# sw63_mk3.net
KiCad netlist of a schematic drawn in EAGLE
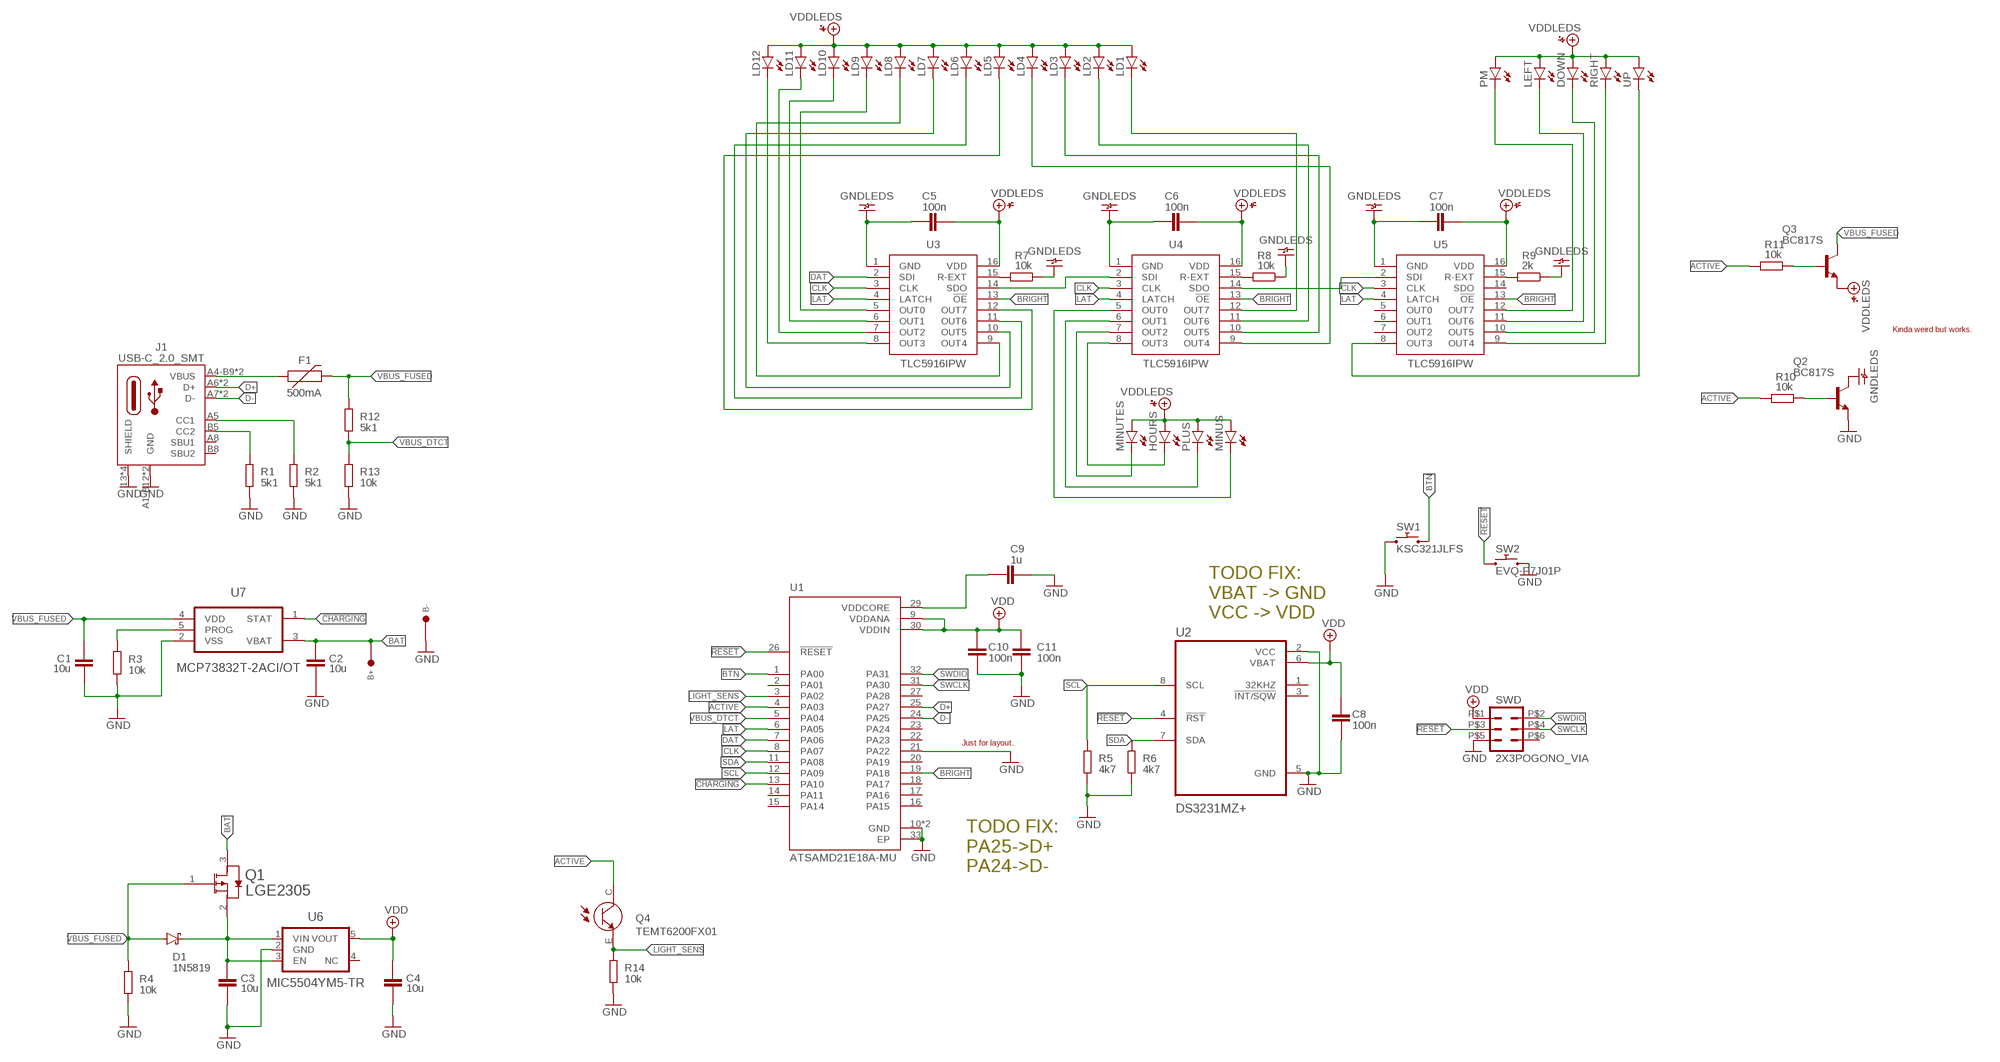
[diagram p0: schematic, sheet 1]

(export (version "E")
  (design (tool "Eeschema 10.0.6"))
  (components
    (comp (ref "B+")
      (value "TEST_PIN_LARGE")
      (footprint "eagle-import:TEST_PIN_2.0")
      (libsource (lib "eagle-import") (part "TEST_PIN_LARGE"))
    )
    (comp (ref "B-")
      (value "TEST_PIN_LARGE")
      (footprint "eagle-import:TEST_PIN_2.0")
      (libsource (lib "eagle-import") (part "TEST_PIN_LARGE"))
    )
    (comp (ref "C1")
      (value "10u")
      (footprint "eagle-import:CAPACITOR0805")
      (libsource (lib "eagle-import") (part "CAPACITOR0805"))
    )
    (comp (ref "C2")
      (value "10u")
      (footprint "eagle-import:CAPACITOR0805")
      (libsource (lib "eagle-import") (part "CAPACITOR0805"))
    )
    (comp (ref "C3")
      (value "10u")
      (footprint "eagle-import:CAPACITOR0805")
      (libsource (lib "eagle-import") (part "CAPACITOR0805"))
    )
    (comp (ref "C4")
      (value "10u")
      (footprint "eagle-import:CAPACITOR0805")
      (libsource (lib "eagle-import") (part "CAPACITOR0805"))
    )
    (comp (ref "C5")
      (value "100n")
      (footprint "eagle-import:CAPACITOR0603")
      (libsource (lib "eagle-import") (part "CAPACITOR0603"))
    )
    (comp (ref "C6")
      (value "100n")
      (footprint "eagle-import:CAPACITOR0603")
      (libsource (lib "eagle-import") (part "CAPACITOR0603"))
    )
    (comp (ref "C7")
      (value "100n")
      (footprint "eagle-import:CAPACITOR0603")
      (libsource (lib "eagle-import") (part "CAPACITOR0603"))
    )
    (comp (ref "C8")
      (value "100n")
      (footprint "eagle-import:CAPACITOR0603")
      (libsource (lib "eagle-import") (part "CAPACITOR0603"))
    )
    (comp (ref "C9")
      (value "1u")
      (footprint "eagle-import:CAPACITOR0603")
      (libsource (lib "eagle-import") (part "CAPACITOR0603"))
    )
    (comp (ref "C10")
      (value "100n")
      (footprint "eagle-import:CAPACITOR0603")
      (libsource (lib "eagle-import") (part "CAPACITOR0603"))
    )
    (comp (ref "C11")
      (value "100n")
      (footprint "eagle-import:CAPACITOR0603")
      (libsource (lib "eagle-import") (part "CAPACITOR0603"))
    )
    (comp (ref "D1")
      (value "1N5819")
      (footprint "eagle-import:SOD123")
      (libsource (lib "eagle-import") (part "SCHOTTKY_DIODE"))
    )
    (comp (ref "DOWN")
      (value "LED_RECT-3.2X2")
      (footprint "eagle-import:LED_RECT_3.2X2")
      (libsource (lib "eagle-import") (part "LED_RECT-3.2X2"))
    )
    (comp (ref "F1")
      (value "500mA")
      (footprint "eagle-import:PTC0805")
      (libsource (lib "eagle-import") (part "PTC"))
    )
    (comp (ref "HOURS")
      (value "LED_THT-5MM_B")
      (footprint "eagle-import:LED_5MM_BLUE")
      (libsource (lib "eagle-import") (part "LED_THT-5MM_B"))
    )
    (comp (ref "J1")
      (value "USB-C_2.0_SMT")
      (footprint "eagle-import:USB-C_FULL_SMT")
      (libsource (lib "eagle-import") (part "USB-C_2.0_SMT"))
    )
    (comp (ref "LD1")
      (value "LED_SMT_1206")
      (footprint "eagle-import:LED_1206")
      (libsource (lib "eagle-import") (part "LED_SMT_1206"))
    )
    (comp (ref "LD2")
      (value "LED_SMT_1206")
      (footprint "eagle-import:LED_1206")
      (libsource (lib "eagle-import") (part "LED_SMT_1206"))
    )
    (comp (ref "LD3")
      (value "LED_SMT_1206")
      (footprint "eagle-import:LED_1206")
      (libsource (lib "eagle-import") (part "LED_SMT_1206"))
    )
    (comp (ref "LD4")
      (value "LED_SMT_1206")
      (footprint "eagle-import:LED_1206")
      (libsource (lib "eagle-import") (part "LED_SMT_1206"))
    )
    (comp (ref "LD5")
      (value "LED_SMT_1206")
      (footprint "eagle-import:LED_1206")
      (libsource (lib "eagle-import") (part "LED_SMT_1206"))
    )
    (comp (ref "LD6")
      (value "LED_SMT_1206")
      (footprint "eagle-import:LED_1206")
      (libsource (lib "eagle-import") (part "LED_SMT_1206"))
    )
    (comp (ref "LD7")
      (value "LED_SMT_1206")
      (footprint "eagle-import:LED_1206")
      (libsource (lib "eagle-import") (part "LED_SMT_1206"))
    )
    (comp (ref "LD8")
      (value "LED_SMT_1206")
      (footprint "eagle-import:LED_1206")
      (libsource (lib "eagle-import") (part "LED_SMT_1206"))
    )
    (comp (ref "LD9")
      (value "LED_SMT_1206")
      (footprint "eagle-import:LED_1206")
      (libsource (lib "eagle-import") (part "LED_SMT_1206"))
    )
    (comp (ref "LD10")
      (value "LED_SMT_1206")
      (footprint "eagle-import:LED_1206")
      (libsource (lib "eagle-import") (part "LED_SMT_1206"))
    )
    (comp (ref "LD11")
      (value "LED_SMT_1206")
      (footprint "eagle-import:LED_1206")
      (libsource (lib "eagle-import") (part "LED_SMT_1206"))
    )
    (comp (ref "LD12")
      (value "LED_SMT_1206")
      (footprint "eagle-import:LED_1206")
      (libsource (lib "eagle-import") (part "LED_SMT_1206"))
    )
    (comp (ref "LEFT")
      (value "LED_RECT-3.2X2")
      (footprint "eagle-import:LED_RECT_3.2X2")
      (libsource (lib "eagle-import") (part "LED_RECT-3.2X2"))
    )
    (comp (ref "MINUS")
      (value "LED_THT-5MM_R")
      (footprint "eagle-import:LED_5MM_RED")
      (libsource (lib "eagle-import") (part "LED_THT-5MM_R"))
    )
    (comp (ref "MINUTES")
      (value "LED_THT-5MM_Y")
      (footprint "eagle-import:LED_5MM_YELLOW")
      (libsource (lib "eagle-import") (part "LED_THT-5MM_Y"))
    )
    (comp (ref "PLUS")
      (value "LED_THT-5MM_G")
      (footprint "eagle-import:LED_5MM_GREEN")
      (libsource (lib "eagle-import") (part "LED_THT-5MM_G"))
    )
    (comp (ref "PM")
      (value "LED_THT-3MM_ALT")
      (footprint "eagle-import:LED_3MM_ALT")
      (libsource (lib "eagle-import") (part "LED_THT-3MM_ALT"))
    )
    (comp (ref "Q1")
      (value "LGE2305")
      (footprint "eagle-import:SOT23")
      (libsource (lib "eagle-import") (part "LGE2305"))
    )
    (comp (ref "Q2")
      (value "BC817S")
      (footprint "eagle-import:SOT23")
      (libsource (lib "eagle-import") (part "BC817S"))
    )
    (comp (ref "Q3")
      (value "BC817S")
      (footprint "eagle-import:SOT23")
      (libsource (lib "eagle-import") (part "BC817S"))
    )
    (comp (ref "Q4")
      (value "TEMT6200FX01")
      (footprint "eagle-import:TEMT6200FX01")
      (fields (field (name "MF") "Vishay Semiconductor"))
      (libsource (lib "eagle-import") (part "TEMT6200FX01"))
    )
    (comp (ref "R1")
      (value "5k1")
      (footprint "eagle-import:RESISTOR0603")
      (libsource (lib "eagle-import") (part "RESISTOR0603"))
    )
    (comp (ref "R2")
      (value "5k1")
      (footprint "eagle-import:RESISTOR0603")
      (libsource (lib "eagle-import") (part "RESISTOR0603"))
    )
    (comp (ref "R3")
      (value "10k")
      (footprint "eagle-import:RESISTOR0603")
      (libsource (lib "eagle-import") (part "RESISTOR0603"))
    )
    (comp (ref "R4")
      (value "10k")
      (footprint "eagle-import:RESISTOR0603")
      (libsource (lib "eagle-import") (part "RESISTOR0603"))
    )
    (comp (ref "R5")
      (value "4k7")
      (footprint "eagle-import:RESISTOR0603")
      (libsource (lib "eagle-import") (part "RESISTOR0603"))
    )
    (comp (ref "R6")
      (value "4k7")
      (footprint "eagle-import:RESISTOR0603")
      (libsource (lib "eagle-import") (part "RESISTOR0603"))
    )
    (comp (ref "R7")
      (value "10k")
      (footprint "eagle-import:RESISTOR0603")
      (libsource (lib "eagle-import") (part "RESISTOR0603"))
    )
    (comp (ref "R8")
      (value "10k")
      (footprint "eagle-import:RESISTOR0603")
      (libsource (lib "eagle-import") (part "RESISTOR0603"))
    )
    (comp (ref "R9")
      (value "2k")
      (footprint "eagle-import:RESISTOR0603")
      (libsource (lib "eagle-import") (part "RESISTOR0603"))
    )
    (comp (ref "R10")
      (value "10k")
      (footprint "eagle-import:RESISTOR0603")
      (libsource (lib "eagle-import") (part "RESISTOR0603"))
    )
    (comp (ref "R11")
      (value "10k")
      (footprint "eagle-import:RESISTOR0603")
      (libsource (lib "eagle-import") (part "RESISTOR0603"))
    )
    (comp (ref "R12")
      (value "5k1")
      (footprint "eagle-import:RESISTOR0603")
      (libsource (lib "eagle-import") (part "RESISTOR0603"))
    )
    (comp (ref "R13")
      (value "10k")
      (footprint "eagle-import:RESISTOR0603")
      (libsource (lib "eagle-import") (part "RESISTOR0603"))
    )
    (comp (ref "R14")
      (value "10k")
      (footprint "eagle-import:RESISTOR0603")
      (libsource (lib "eagle-import") (part "RESISTOR0603"))
    )
    (comp (ref "RIGHT")
      (value "LED_RECT-3.2X2")
      (footprint "eagle-import:LED_RECT_3.2X2")
      (libsource (lib "eagle-import") (part "LED_RECT-3.2X2"))
    )
    (comp (ref "SW1")
      (value "KSC321JLFS")
      (footprint "eagle-import:KSC3XXJ")
      (libsource (lib "eagle-import") (part "KSC3XXJ"))
    )
    (comp (ref "SW2")
      (value "EVQ-P7J01P")
      (footprint "eagle-import:EVQ-P7J01P")
      (libsource (lib "eagle-import") (part "EVQ-P7J01P"))
    )
    (comp (ref "SWD")
      (value "2X3POGONO_VIA")
      (footprint "eagle-import:2X3_POGO_NO_VIA")
      (libsource (lib "eagle-import") (part "2X3POGONO_VIA"))
    )
    (comp (ref "U1")
      (value "ATSAMD21E18A-MU")
      (footprint "eagle-import:QFN50P500X500X100-33N")
      (fields (field (name "DIGIKEY_PART_NUMBER") "ATSAMD21E18A-MU-ND") (field (name "MF") "Microchip"))
      (libsource (lib "eagle-import") (part "ATSAMD21E18A-MU"))
    )
    (comp (ref "U2")
      (value "DS3231MZ+")
      (footprint "eagle-import:SO8")
      (fields
        (field (name "DIGI-KEY_PART_NUMBER") "DS3231MZ+-ND")
        (field (name "MF") "Maxim Integrated Products")
      )
      (libsource (lib "eagle-import") (part "DS3231MZ+"))
    )
    (comp (ref "U3")
      (value "TLC5916IPW")
      (footprint "eagle-import:TSSOP16")
      (libsource (lib "eagle-import") (part "TLC5916IPW"))
    )
    (comp (ref "U4")
      (value "TLC5916IPW")
      (footprint "eagle-import:TSSOP16")
      (libsource (lib "eagle-import") (part "TLC5916IPW"))
    )
    (comp (ref "U5")
      (value "TLC5916IPW")
      (footprint "eagle-import:TSSOP16")
      (libsource (lib "eagle-import") (part "TLC5916IPW"))
    )
    (comp (ref "U6")
      (value "MIC5504YM5-TR")
      (footprint "eagle-import:SOT23-5")
      (libsource (lib "eagle-import") (part "MIC5504YM5-TR"))
    )
    (comp (ref "U7")
      (value "MCP73832T-2ACI/OT")
      (footprint "eagle-import:SOT23-5")
      (fields (field (name "MPN") "MCP73831T-2ACI/OT"))
      (libsource (lib "eagle-import") (part "MCP73831T-2ACI"))
    )
    (comp (ref "UP")
      (value "LED_RECT-3.2X2")
      (footprint "eagle-import:LED_RECT_3.2X2")
      (libsource (lib "eagle-import") (part "LED_RECT-3.2X2"))
    )
  )
  (nets
    (net (code "1") (name "/~{CHARGING}") (class "Default")
      (node (ref "U1") (pin "13") (pinfunction "PA10_13") (pintype "bidirectional"))
      (node (ref "U7") (pin "1") (pinfunction "STAT_1") (pintype "output"))
    )
    (net (code "2") (name "/~{RESET}") (class "Default")
      (node (ref "SW2") (pin "1_1") (pinfunction "1_1_1") (pintype "passive"))
      (node (ref "SW2") (pin "1_2") (pinfunction "1_1_2") (pintype "passive"))
      (node (ref "SWD") (pin "P$3") (pinfunction "3_P$3") (pintype "passive"))
      (node (ref "U1") (pin "26") (pinfunction "~{RESET}_26") (pintype "input"))
      (node (ref "U2") (pin "4") (pinfunction "~{RST}_4") (pintype "bidirectional"))
    )
    (net (code "3") (name "ACTIVE") (class "Default")
      (node (ref "Q4") (pin "C") (pinfunction "C_C") (pintype "passive"))
      (node (ref "R10") (pin "2") (pinfunction "2_2") (pintype "passive"))
      (node (ref "R11") (pin "2") (pinfunction "2_2") (pintype "passive"))
      (node (ref "U1") (pin "4") (pinfunction "PA03_4") (pintype "bidirectional"))
    )
    (net (code "4") (name "BAT") (class "Default")
      (node (ref "B+") (pin "P$1") (pinfunction "P$1_P$1") (pintype "bidirectional"))
      (node (ref "C2") (pin "1") (pinfunction "1_1") (pintype "passive"))
      (node (ref "Q1") (pin "3") (pinfunction "DRAIN_3") (pintype "passive"))
      (node (ref "U7") (pin "3") (pinfunction "VBAT_3") (pintype "output"))
    )
    (net (code "5") (name "BRIGHT") (class "Default")
      (node (ref "U1") (pin "19") (pinfunction "PA18_19") (pintype "bidirectional"))
      (node (ref "U3") (pin "13") (pinfunction "~{OE}_13") (pintype "input"))
      (node (ref "U4") (pin "13") (pinfunction "~{OE}_13") (pintype "input"))
      (node (ref "U5") (pin "13") (pinfunction "~{OE}_13") (pintype "input"))
    )
    (net (code "6") (name "BTN") (class "Default")
      (node (ref "SW1") (pin "2") (pinfunction "2_2") (pintype "passive"))
      (node (ref "SW1") (pin "4") (pinfunction "2_4") (pintype "passive"))
      (node (ref "U1") (pin "1") (pinfunction "PA00_1") (pintype "bidirectional"))
    )
    (net (code "7") (name "CLK") (class "Default")
      (node (ref "U1") (pin "8") (pinfunction "PA07_8") (pintype "bidirectional"))
      (node (ref "U3") (pin "3") (pinfunction "CLK_3") (pintype "input"))
      (node (ref "U4") (pin "3") (pinfunction "CLK_3") (pintype "input"))
      (node (ref "U5") (pin "3") (pinfunction "CLK_3") (pintype "input"))
    )
    (net (code "8") (name "D+") (class "Default")
      (node (ref "J1") (pin "A6") (pinfunction "D+_A6") (pintype "bidirectional"))
      (node (ref "J1") (pin "B6") (pinfunction "D+_B6") (pintype "bidirectional"))
      (node (ref "U1") (pin "25") (pinfunction "PA27_25") (pintype "bidirectional"))
    )
    (net (code "9") (name "D-") (class "Default")
      (node (ref "J1") (pin "A7") (pinfunction "D-_A7") (pintype "bidirectional"))
      (node (ref "J1") (pin "B7") (pinfunction "D-_B7") (pintype "bidirectional"))
      (node (ref "U1") (pin "24") (pinfunction "PA25_24") (pintype "bidirectional"))
    )
    (net (code "10") (name "DAT") (class "Default")
      (node (ref "U1") (pin "7") (pinfunction "PA06_7") (pintype "bidirectional"))
      (node (ref "U3") (pin "2") (pinfunction "SDI_2") (pintype "input"))
    )
    (net (code "11") (name "GND") (class "Default")
      (node (ref "B-") (pin "P$1") (pinfunction "P$1_P$1") (pintype "bidirectional"))
      (node (ref "C1") (pin "2") (pinfunction "2_2") (pintype "passive"))
      (node (ref "C10") (pin "1") (pinfunction "1_1") (pintype "passive"))
      (node (ref "C11") (pin "1") (pinfunction "1_1") (pintype "passive"))
      (node (ref "C2") (pin "2") (pinfunction "2_2") (pintype "passive"))
      (node (ref "C3") (pin "2") (pinfunction "2_2") (pintype "passive"))
      (node (ref "C4") (pin "2") (pinfunction "2_2") (pintype "passive"))
      (node (ref "C8") (pin "2") (pinfunction "2_2") (pintype "passive"))
      (node (ref "C9") (pin "1") (pinfunction "1_1") (pintype "passive"))
      (node (ref "J1") (pin "13") (pinfunction "SHIELD_13") (pintype "bidirectional"))
      (node (ref "J1") (pin "14") (pinfunction "SHIELD_14") (pintype "bidirectional"))
      (node (ref "J1") (pin "15") (pinfunction "SHIELD_15") (pintype "bidirectional"))
      (node (ref "J1") (pin "16") (pinfunction "SHIELD_16") (pintype "bidirectional"))
      (node (ref "J1") (pin "A1-B12") (pinfunction "GND_A1-B12") (pintype "passive"))
      (node (ref "J1") (pin "B1-A12") (pinfunction "GND_B1-A12") (pintype "passive"))
      (node (ref "Q2") (pin "2") (pinfunction "E_2") (pintype "passive"))
      (node (ref "R1") (pin "1") (pinfunction "1_1") (pintype "passive"))
      (node (ref "R13") (pin "1") (pinfunction "1_1") (pintype "passive"))
      (node (ref "R14") (pin "1") (pinfunction "1_1") (pintype "passive"))
      (node (ref "R2") (pin "1") (pinfunction "1_1") (pintype "passive"))
      (node (ref "R3") (pin "1") (pinfunction "1_1") (pintype "passive"))
      (node (ref "R4") (pin "1") (pinfunction "1_1") (pintype "passive"))
      (node (ref "R5") (pin "1") (pinfunction "1_1") (pintype "passive"))
      (node (ref "R6") (pin "1") (pinfunction "1_1") (pintype "passive"))
      (node (ref "SW1") (pin "1") (pinfunction "1_1") (pintype "passive"))
      (node (ref "SW1") (pin "3") (pinfunction "1_3") (pintype "passive"))
      (node (ref "SW2") (pin "2_1") (pinfunction "2_2_1") (pintype "passive"))
      (node (ref "SW2") (pin "2_2") (pinfunction "2_2_2") (pintype "passive"))
      (node (ref "SWD") (pin "P$5") (pinfunction "5_P$5") (pintype "passive"))
      (node (ref "U1") (pin "10") (pinfunction "GND_10") (pintype "power_in"))
      (node (ref "U1") (pin "21") (pinfunction "PA22_21") (pintype "bidirectional"))
      (node (ref "U1") (pin "28") (pinfunction "GND_28") (pintype "power_in"))
      (node (ref "U1") (pin "33") (pinfunction "EP_33") (pintype "power_in"))
      (node (ref "U2") (pin "2") (pinfunction "VCC_2") (pintype "power_in"))
      (node (ref "U2") (pin "5") (pinfunction "GND_5") (pintype "power_in"))
      (node (ref "U6") (pin "2") (pinfunction "GND_2") (pintype "power_in"))
      (node (ref "U7") (pin "2") (pinfunction "VSS_2") (pintype "power_in"))
    )
    (net (code "12") (name "GNDLEDS") (class "Default")
      (node (ref "C5") (pin "1") (pinfunction "1_1") (pintype "passive"))
      (node (ref "C6") (pin "1") (pinfunction "1_1") (pintype "passive"))
      (node (ref "C7") (pin "1") (pinfunction "1_1") (pintype "passive"))
      (node (ref "Q2") (pin "3") (pinfunction "C_3") (pintype "passive"))
      (node (ref "R7") (pin "1") (pinfunction "1_1") (pintype "passive"))
      (node (ref "R8") (pin "1") (pinfunction "1_1") (pintype "passive"))
      (node (ref "R9") (pin "1") (pinfunction "1_1") (pintype "passive"))
      (node (ref "U3") (pin "1") (pinfunction "GND_1") (pintype "power_in"))
      (node (ref "U4") (pin "1") (pinfunction "GND_1") (pintype "power_in"))
      (node (ref "U5") (pin "1") (pinfunction "GND_1") (pintype "power_in"))
    )
    (net (code "13") (name "LAT") (class "Default")
      (node (ref "U1") (pin "6") (pinfunction "PA05_6") (pintype "bidirectional"))
      (node (ref "U3") (pin "4") (pinfunction "LATCH_4") (pintype "input"))
      (node (ref "U4") (pin "4") (pinfunction "LATCH_4") (pintype "input"))
      (node (ref "U5") (pin "4") (pinfunction "LATCH_4") (pintype "input"))
    )
    (net (code "14") (name "LIGHT_SENS") (class "Default")
      (node (ref "Q4") (pin "E") (pinfunction "E_E") (pintype "passive"))
      (node (ref "R14") (pin "2") (pinfunction "2_2") (pintype "passive"))
      (node (ref "U1") (pin "3") (pinfunction "PA02_3") (pintype "bidirectional"))
    )
    (net (code "15") (name "Net-(DOWN-C)") (class "Default")
      (node (ref "DOWN") (pin "K") (pinfunction "C_K") (pintype "passive"))
      (node (ref "U5") (pin "10") (pinfunction "OUT5_10") (pintype "output"))
    )
    (net (code "16") (name "Net-(F1-1)") (class "Default")
      (node (ref "F1") (pin "2") (pinfunction "1_2") (pintype "bidirectional"))
      (node (ref "J1") (pin "A4-B9") (pinfunction "VBUS_A4-B9") (pintype "power_in"))
      (node (ref "J1") (pin "B4-A9") (pinfunction "VBUS_B4-A9") (pintype "power_in"))
    )
    (net (code "17") (name "Net-(HOURS-C)") (class "Default")
      (node (ref "HOURS") (pin "K") (pinfunction "C_K") (pintype "passive"))
      (node (ref "U4") (pin "8") (pinfunction "OUT3_8") (pintype "output"))
    )
    (net (code "18") (name "Net-(J1-CC1)") (class "Default")
      (node (ref "J1") (pin "A5") (pinfunction "CC1_A5") (pintype "bidirectional"))
      (node (ref "R2") (pin "2") (pinfunction "2_2") (pintype "passive"))
    )
    (net (code "19") (name "Net-(J1-CC2)") (class "Default")
      (node (ref "J1") (pin "B5") (pinfunction "CC2_B5") (pintype "bidirectional"))
      (node (ref "R1") (pin "2") (pinfunction "2_2") (pintype "passive"))
    )
    (net (code "20") (name "Net-(LEFT-C)") (class "Default")
      (node (ref "LEFT") (pin "K") (pinfunction "C_K") (pintype "passive"))
      (node (ref "U5") (pin "11") (pinfunction "OUT6_11") (pintype "output"))
    )
    (net (code "21") (name "Net-(MINUS-C)") (class "Default")
      (node (ref "MINUS") (pin "K") (pinfunction "C_K") (pintype "passive"))
      (node (ref "U4") (pin "5") (pinfunction "OUT0_5") (pintype "output"))
    )
    (net (code "22") (name "Net-(MINUTES-C)") (class "Default")
      (node (ref "MINUTES") (pin "K") (pinfunction "C_K") (pintype "passive"))
      (node (ref "U4") (pin "7") (pinfunction "OUT2_7") (pintype "output"))
    )
    (net (code "23") (name "Net-(PLUS-C)") (class "Default")
      (node (ref "PLUS") (pin "K") (pinfunction "C_K") (pintype "passive"))
      (node (ref "U4") (pin "6") (pinfunction "OUT1_6") (pintype "output"))
    )
    (net (code "24") (name "Net-(PM-C)") (class "Default")
      (node (ref "PM") (pin "K") (pinfunction "C_K") (pintype "passive"))
      (node (ref "U5") (pin "12") (pinfunction "OUT7_12") (pintype "output"))
    )
    (net (code "25") (name "Net-(Q1-SOURCE)") (class "Default")
      (node (ref "C3") (pin "1") (pinfunction "1_1") (pintype "passive"))
      (node (ref "D1") (pin "C") (pinfunction "C_C") (pintype "passive"))
      (node (ref "Q1") (pin "2") (pinfunction "SOURCE_2") (pintype "passive"))
      (node (ref "U6") (pin "1") (pinfunction "VIN_1") (pintype "input"))
      (node (ref "U6") (pin "3") (pinfunction "EN_3") (pintype "input"))
    )
    (net (code "26") (name "Net-(Q2-B)") (class "Default")
      (node (ref "Q2") (pin "1") (pinfunction "B_1") (pintype "passive"))
      (node (ref "R10") (pin "1") (pinfunction "1_1") (pintype "passive"))
    )
    (net (code "27") (name "Net-(Q3-B)") (class "Default")
      (node (ref "Q3") (pin "1") (pinfunction "B_1") (pintype "passive"))
      (node (ref "R11") (pin "1") (pinfunction "1_1") (pintype "passive"))
    )
    (net (code "28") (name "Net-(RIGHT-C)") (class "Default")
      (node (ref "RIGHT") (pin "K") (pinfunction "C_K") (pintype "passive"))
      (node (ref "U5") (pin "9") (pinfunction "OUT4_9") (pintype "output"))
    )
    (net (code "29") (name "Net-(U1-VDDCORE)") (class "Default")
      (node (ref "C9") (pin "2") (pinfunction "2_2") (pintype "passive"))
      (node (ref "U1") (pin "29") (pinfunction "VDDCORE_29") (pintype "power_in"))
    )
    (net (code "30") (name "Net-(U3-OUT0)") (class "Default")
      (node (ref "LD9") (pin "C") (pinfunction "C_C") (pintype "passive"))
      (node (ref "U3") (pin "5") (pinfunction "OUT0_5") (pintype "output"))
    )
    (net (code "31") (name "Net-(U3-OUT1)") (class "Default")
      (node (ref "LD10") (pin "C") (pinfunction "C_C") (pintype "passive"))
      (node (ref "U3") (pin "6") (pinfunction "OUT1_6") (pintype "output"))
    )
    (net (code "32") (name "Net-(U3-OUT2)") (class "Default")
      (node (ref "LD11") (pin "C") (pinfunction "C_C") (pintype "passive"))
      (node (ref "U3") (pin "7") (pinfunction "OUT2_7") (pintype "output"))
    )
    (net (code "33") (name "Net-(U3-OUT3)") (class "Default")
      (node (ref "LD12") (pin "C") (pinfunction "C_C") (pintype "passive"))
      (node (ref "U3") (pin "8") (pinfunction "OUT3_8") (pintype "output"))
    )
    (net (code "34") (name "Net-(U3-OUT4)") (class "Default")
      (node (ref "LD8") (pin "C") (pinfunction "C_C") (pintype "passive"))
      (node (ref "U3") (pin "9") (pinfunction "OUT4_9") (pintype "output"))
    )
    (net (code "35") (name "Net-(U3-OUT5)") (class "Default")
      (node (ref "LD7") (pin "C") (pinfunction "C_C") (pintype "passive"))
      (node (ref "U3") (pin "10") (pinfunction "OUT5_10") (pintype "output"))
    )
    (net (code "36") (name "Net-(U3-OUT6)") (class "Default")
      (node (ref "LD6") (pin "C") (pinfunction "C_C") (pintype "passive"))
      (node (ref "U3") (pin "11") (pinfunction "OUT6_11") (pintype "output"))
    )
    (net (code "37") (name "Net-(U3-OUT7)") (class "Default")
      (node (ref "LD5") (pin "C") (pinfunction "C_C") (pintype "passive"))
      (node (ref "U3") (pin "12") (pinfunction "OUT7_12") (pintype "output"))
    )
    (net (code "38") (name "Net-(U3-R-EXT)") (class "Default")
      (node (ref "R7") (pin "2") (pinfunction "2_2") (pintype "passive"))
      (node (ref "U3") (pin "15") (pinfunction "R-EXT_15") (pintype "input"))
    )
    (net (code "39") (name "Net-(U3-SDO)") (class "Default")
      (node (ref "U3") (pin "14") (pinfunction "SDO_14") (pintype "output"))
      (node (ref "U4") (pin "2") (pinfunction "SDI_2") (pintype "input"))
    )
    (net (code "40") (name "Net-(U4-OUT4)") (class "Default")
      (node (ref "LD4") (pin "C") (pinfunction "C_C") (pintype "passive"))
      (node (ref "U4") (pin "9") (pinfunction "OUT4_9") (pintype "output"))
    )
    (net (code "41") (name "Net-(U4-OUT5)") (class "Default")
      (node (ref "LD3") (pin "C") (pinfunction "C_C") (pintype "passive"))
      (node (ref "U4") (pin "10") (pinfunction "OUT5_10") (pintype "output"))
    )
    (net (code "42") (name "Net-(U4-OUT6)") (class "Default")
      (node (ref "LD2") (pin "C") (pinfunction "C_C") (pintype "passive"))
      (node (ref "U4") (pin "11") (pinfunction "OUT6_11") (pintype "output"))
    )
    (net (code "43") (name "Net-(U4-OUT7)") (class "Default")
      (node (ref "LD1") (pin "C") (pinfunction "C_C") (pintype "passive"))
      (node (ref "U4") (pin "12") (pinfunction "OUT7_12") (pintype "output"))
    )
    (net (code "44") (name "Net-(U4-R-EXT)") (class "Default")
      (node (ref "R8") (pin "2") (pinfunction "2_2") (pintype "passive"))
      (node (ref "U4") (pin "15") (pinfunction "R-EXT_15") (pintype "input"))
    )
    (net (code "45") (name "Net-(U4-SDO)") (class "Default")
      (node (ref "U4") (pin "14") (pinfunction "SDO_14") (pintype "output"))
      (node (ref "U5") (pin "2") (pinfunction "SDI_2") (pintype "input"))
    )
    (net (code "46") (name "Net-(U5-OUT3)") (class "Default")
      (node (ref "U5") (pin "8") (pinfunction "OUT3_8") (pintype "output"))
      (node (ref "UP") (pin "K") (pinfunction "C_K") (pintype "passive"))
    )
    (net (code "47") (name "Net-(U5-R-EXT)") (class "Default")
      (node (ref "R9") (pin "2") (pinfunction "2_2") (pintype "passive"))
      (node (ref "U5") (pin "15") (pinfunction "R-EXT_15") (pintype "input"))
    )
    (net (code "48") (name "Net-(U7-PROG)") (class "Default")
      (node (ref "R3") (pin "2") (pinfunction "2_2") (pintype "passive"))
      (node (ref "U7") (pin "5") (pinfunction "PROG_5") (pintype "input"))
    )
    (net (code "49") (name "SCL") (class "Default")
      (node (ref "R5") (pin "2") (pinfunction "2_2") (pintype "passive"))
      (node (ref "U1") (pin "12") (pinfunction "PA09_12") (pintype "bidirectional"))
      (node (ref "U2") (pin "8") (pinfunction "SCL_8") (pintype "input"))
    )
    (net (code "50") (name "SDA") (class "Default")
      (node (ref "R6") (pin "2") (pinfunction "2_2") (pintype "passive"))
      (node (ref "U1") (pin "11") (pinfunction "PA08_11") (pintype "bidirectional"))
      (node (ref "U2") (pin "7") (pinfunction "SDA_7") (pintype "bidirectional"))
    )
    (net (code "51") (name "SWCLK") (class "Default")
      (node (ref "SWD") (pin "P$4") (pinfunction "4_P$4") (pintype "passive"))
      (node (ref "U1") (pin "31") (pinfunction "PA30_31") (pintype "bidirectional"))
    )
    (net (code "52") (name "SWDIO") (class "Default")
      (node (ref "SWD") (pin "P$2") (pinfunction "2_P$2") (pintype "passive"))
      (node (ref "U1") (pin "32") (pinfunction "PA31_32") (pintype "bidirectional"))
    )
    (net (code "53") (name "VBUS_DTCT") (class "Default")
      (node (ref "R12") (pin "1") (pinfunction "1_1") (pintype "passive"))
      (node (ref "R13") (pin "2") (pinfunction "2_2") (pintype "passive"))
      (node (ref "U1") (pin "5") (pinfunction "PA04_5") (pintype "bidirectional"))
    )
    (net (code "54") (name "VBUS_FUSED") (class "Default")
      (node (ref "C1") (pin "1") (pinfunction "1_1") (pintype "passive"))
      (node (ref "D1") (pin "A") (pinfunction "A_A") (pintype "passive"))
      (node (ref "F1") (pin "3") (pinfunction "2_3") (pintype "bidirectional"))
      (node (ref "Q1") (pin "1") (pinfunction "GATE_1") (pintype "passive"))
      (node (ref "Q3") (pin "3") (pinfunction "C_3") (pintype "passive"))
      (node (ref "R12") (pin "2") (pinfunction "2_2") (pintype "passive"))
      (node (ref "R4") (pin "2") (pinfunction "2_2") (pintype "passive"))
      (node (ref "U7") (pin "4") (pinfunction "VDD_4") (pintype "power_in"))
    )
    (net (code "55") (name "VDD") (class "Default")
      (node (ref "C10") (pin "2") (pinfunction "2_2") (pintype "passive"))
      (node (ref "C11") (pin "2") (pinfunction "2_2") (pintype "passive"))
      (node (ref "C4") (pin "1") (pinfunction "1_1") (pintype "passive"))
      (node (ref "C8") (pin "1") (pinfunction "1_1") (pintype "passive"))
      (node (ref "SWD") (pin "P$1") (pinfunction "1_P$1") (pintype "passive"))
      (node (ref "U1") (pin "30") (pinfunction "VDDIN_30") (pintype "power_in"))
      (node (ref "U1") (pin "9") (pinfunction "VDDANA_9") (pintype "power_in"))
      (node (ref "U2") (pin "6") (pinfunction "VBAT_6") (pintype "power_in"))
      (node (ref "U6") (pin "5") (pinfunction "VOUT_5") (pintype "input"))
    )
    (net (code "56") (name "VDDLEDS") (class "Default")
      (node (ref "C5") (pin "2") (pinfunction "2_2") (pintype "passive"))
      (node (ref "C6") (pin "2") (pinfunction "2_2") (pintype "passive"))
      (node (ref "C7") (pin "2") (pinfunction "2_2") (pintype "passive"))
      (node (ref "DOWN") (pin "A") (pinfunction "A_A") (pintype "passive"))
      (node (ref "HOURS") (pin "A") (pinfunction "A_A") (pintype "passive"))
      (node (ref "LD1") (pin "A") (pinfunction "A_A") (pintype "passive"))
      (node (ref "LD10") (pin "A") (pinfunction "A_A") (pintype "passive"))
      (node (ref "LD11") (pin "A") (pinfunction "A_A") (pintype "passive"))
      (node (ref "LD12") (pin "A") (pinfunction "A_A") (pintype "passive"))
      (node (ref "LD2") (pin "A") (pinfunction "A_A") (pintype "passive"))
      (node (ref "LD3") (pin "A") (pinfunction "A_A") (pintype "passive"))
      (node (ref "LD4") (pin "A") (pinfunction "A_A") (pintype "passive"))
      (node (ref "LD5") (pin "A") (pinfunction "A_A") (pintype "passive"))
      (node (ref "LD6") (pin "A") (pinfunction "A_A") (pintype "passive"))
      (node (ref "LD7") (pin "A") (pinfunction "A_A") (pintype "passive"))
      (node (ref "LD8") (pin "A") (pinfunction "A_A") (pintype "passive"))
      (node (ref "LD9") (pin "A") (pinfunction "A_A") (pintype "passive"))
      (node (ref "LEFT") (pin "A") (pinfunction "A_A") (pintype "passive"))
      (node (ref "MINUS") (pin "A") (pinfunction "A_A") (pintype "passive"))
      (node (ref "MINUTES") (pin "A") (pinfunction "A_A") (pintype "passive"))
      (node (ref "PLUS") (pin "A") (pinfunction "A_A") (pintype "passive"))
      (node (ref "PM") (pin "A") (pinfunction "A_A") (pintype "passive"))
      (node (ref "Q3") (pin "2") (pinfunction "E_2") (pintype "passive"))
      (node (ref "RIGHT") (pin "A") (pinfunction "A_A") (pintype "passive"))
      (node (ref "U3") (pin "16") (pinfunction "VDD_16") (pintype "power_in"))
      (node (ref "U4") (pin "16") (pinfunction "VDD_16") (pintype "power_in"))
      (node (ref "U5") (pin "16") (pinfunction "VDD_16") (pintype "power_in"))
      (node (ref "UP") (pin "A") (pinfunction "A_A") (pintype "passive"))
    )
    (net (code "57") (name "unconnected-(J1-SBU1-PadA8)") (class "Default")
      (node (ref "J1") (pin "A8") (pinfunction "SBU1_A8") (pintype "bidirectional"))
    )
    (net (code "58") (name "unconnected-(J1-SBU2-PadB8)") (class "Default")
      (node (ref "J1") (pin "B8") (pinfunction "SBU2_B8") (pintype "bidirectional"))
    )
    (net (code "59") (name "unconnected-(SWD-6-PadP$6)") (class "Default")
      (node (ref "SWD") (pin "P$6") (pinfunction "6_P$6") (pintype "passive"))
    )
    (net (code "60") (name "unconnected-(U1-PA01-Pad2)") (class "Default")
      (node (ref "U1") (pin "2") (pinfunction "PA01_2") (pintype "bidirectional"))
    )
    (net (code "61") (name "unconnected-(U1-PA11-Pad14)") (class "Default")
      (node (ref "U1") (pin "14") (pinfunction "PA11_14") (pintype "bidirectional"))
    )
    (net (code "62") (name "unconnected-(U1-PA14-Pad15)") (class "Default")
      (node (ref "U1") (pin "15") (pinfunction "PA14_15") (pintype "bidirectional"))
    )
    (net (code "63") (name "unconnected-(U1-PA15-Pad16)") (class "Default")
      (node (ref "U1") (pin "16") (pinfunction "PA15_16") (pintype "bidirectional"))
    )
    (net (code "64") (name "unconnected-(U1-PA16-Pad17)") (class "Default")
      (node (ref "U1") (pin "17") (pinfunction "PA16_17") (pintype "bidirectional"))
    )
    (net (code "65") (name "unconnected-(U1-PA17-Pad18)") (class "Default")
      (node (ref "U1") (pin "18") (pinfunction "PA17_18") (pintype "bidirectional"))
    )
    (net (code "66") (name "unconnected-(U1-PA19-Pad20)") (class "Default")
      (node (ref "U1") (pin "20") (pinfunction "PA19_20") (pintype "bidirectional"))
    )
    (net (code "67") (name "unconnected-(U1-PA23-Pad22)") (class "Default")
      (node (ref "U1") (pin "22") (pinfunction "PA23_22") (pintype "bidirectional"))
    )
    (net (code "68") (name "unconnected-(U1-PA24-Pad23)") (class "Default")
      (node (ref "U1") (pin "23") (pinfunction "PA24_23") (pintype "bidirectional"))
    )
    (net (code "69") (name "unconnected-(U1-PA28-Pad27)") (class "Default")
      (node (ref "U1") (pin "27") (pinfunction "PA28_27") (pintype "bidirectional"))
    )
    (net (code "70") (name "unconnected-(U2-32KHZ-Pad1)") (class "Default")
      (node (ref "U2") (pin "1") (pinfunction "32KHZ_1") (pintype "output"))
    )
    (net (code "71") (name "unconnected-(U2-~{INT{slash}SQW}-Pad3)") (class "Default")
      (node (ref "U2") (pin "3") (pinfunction "~{INT/SQW}_3") (pintype "output"))
    )
    (net (code "72") (name "unconnected-(U5-OUT0-Pad5)") (class "Default")
      (node (ref "U5") (pin "5") (pinfunction "OUT0_5") (pintype "output"))
    )
    (net (code "73") (name "unconnected-(U5-OUT1-Pad6)") (class "Default")
      (node (ref "U5") (pin "6") (pinfunction "OUT1_6") (pintype "output"))
    )
    (net (code "74") (name "unconnected-(U5-OUT2-Pad7)") (class "Default")
      (node (ref "U5") (pin "7") (pinfunction "OUT2_7") (pintype "output"))
    )
    (net (code "75") (name "unconnected-(U5-SDO-Pad14)") (class "Default")
      (node (ref "U5") (pin "14") (pinfunction "SDO_14") (pintype "output"))
    )
    (net (code "76") (name "unconnected-(U6-NC-Pad4)") (class "Default")
      (node (ref "U6") (pin "4") (pinfunction "NC_4") (pintype "no_connect"))
    )
  )
)
